# schematic.net
KiCad netlist of a schematic drawn in EasyEDA
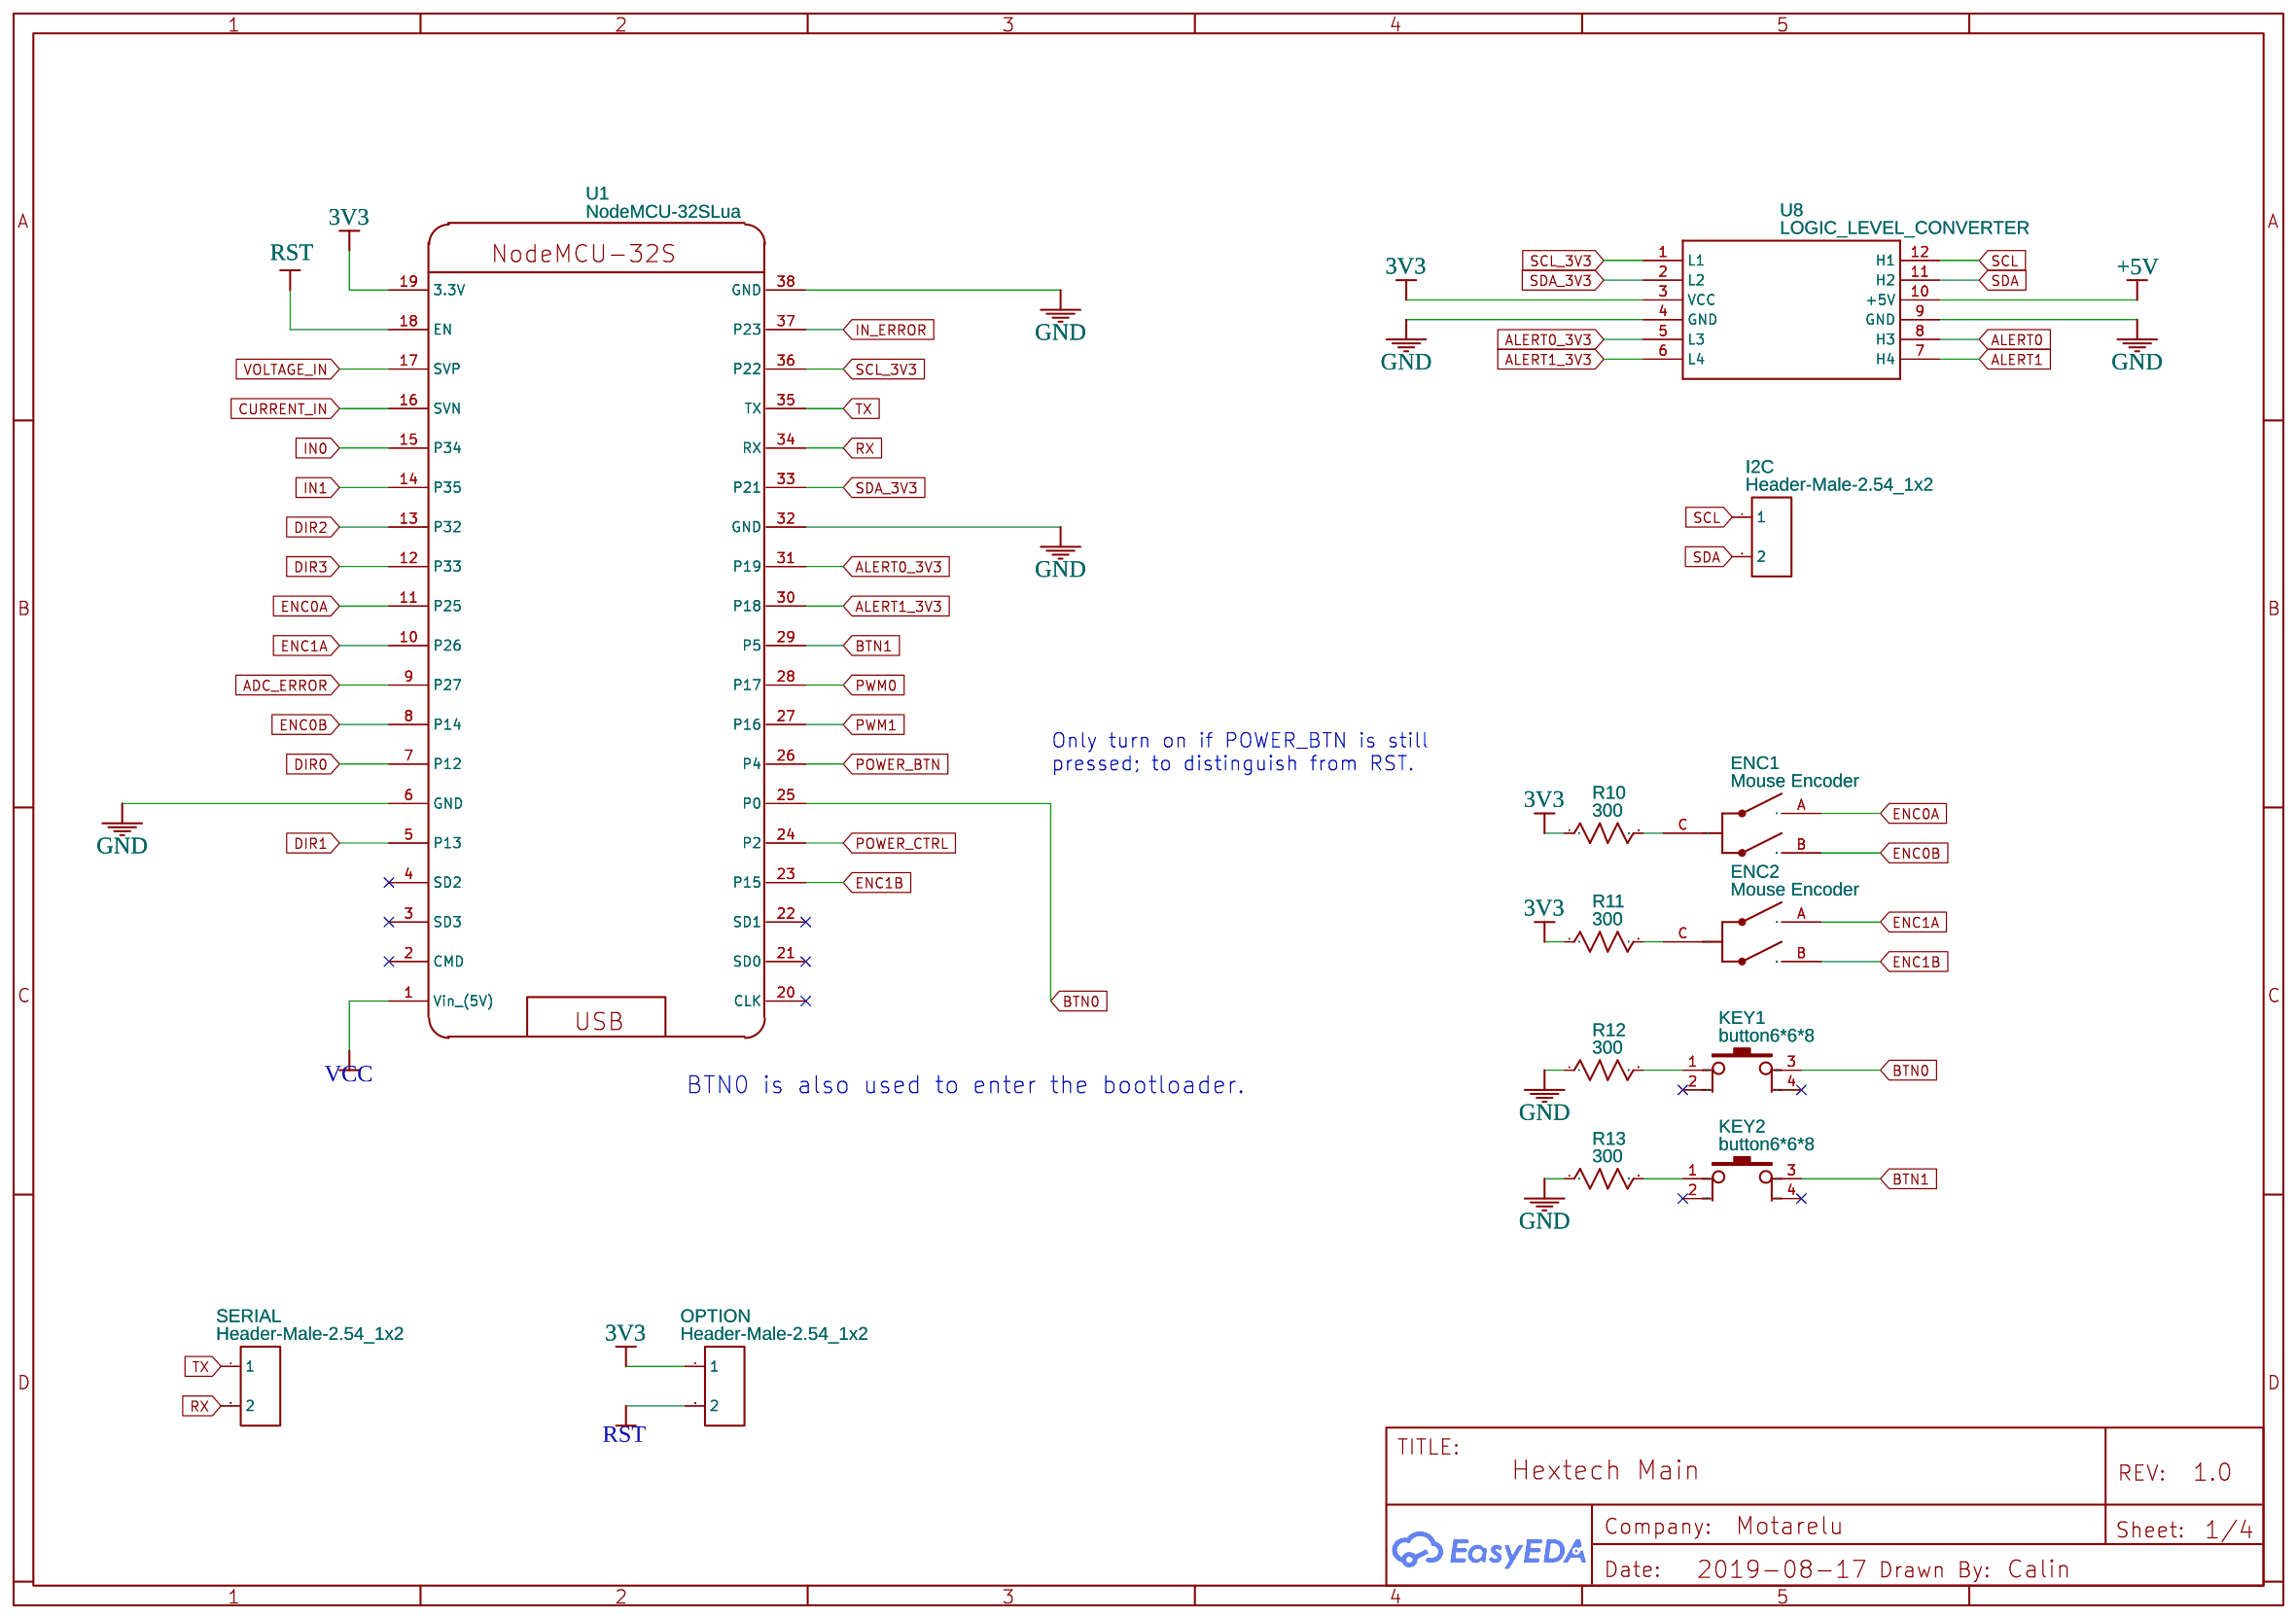
[diagram p0: Main]
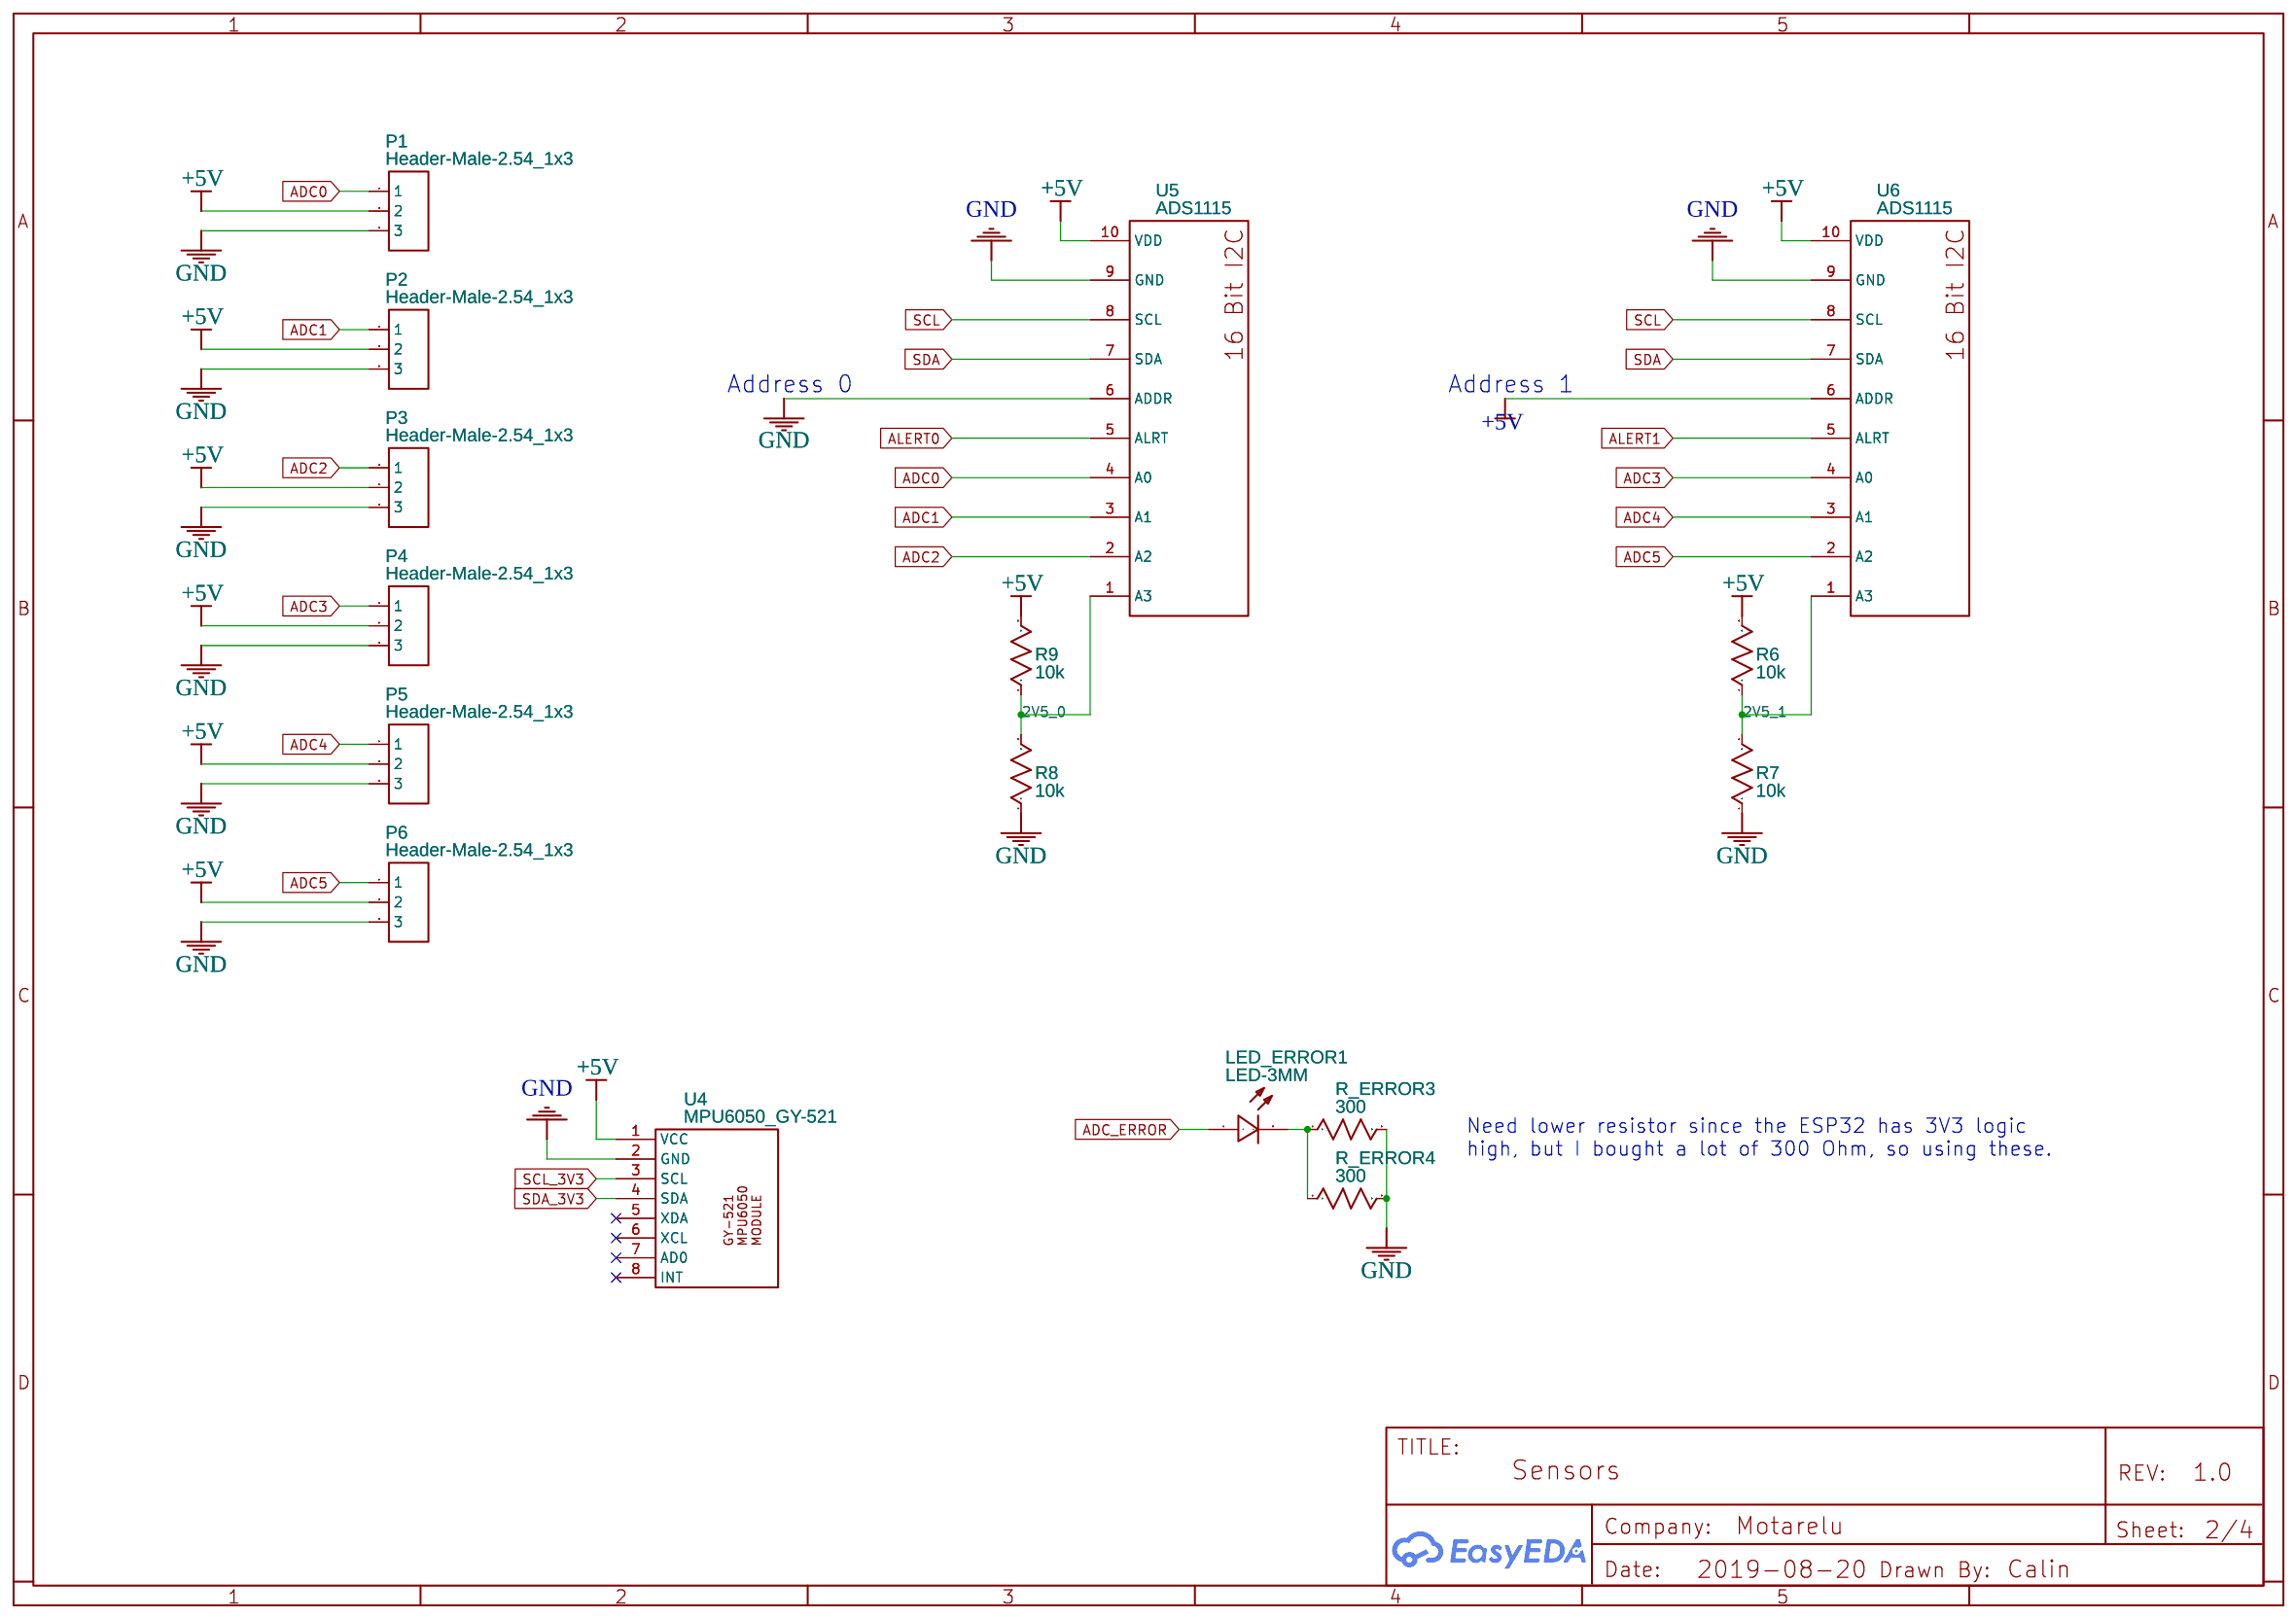
[diagram p1: Sensors]
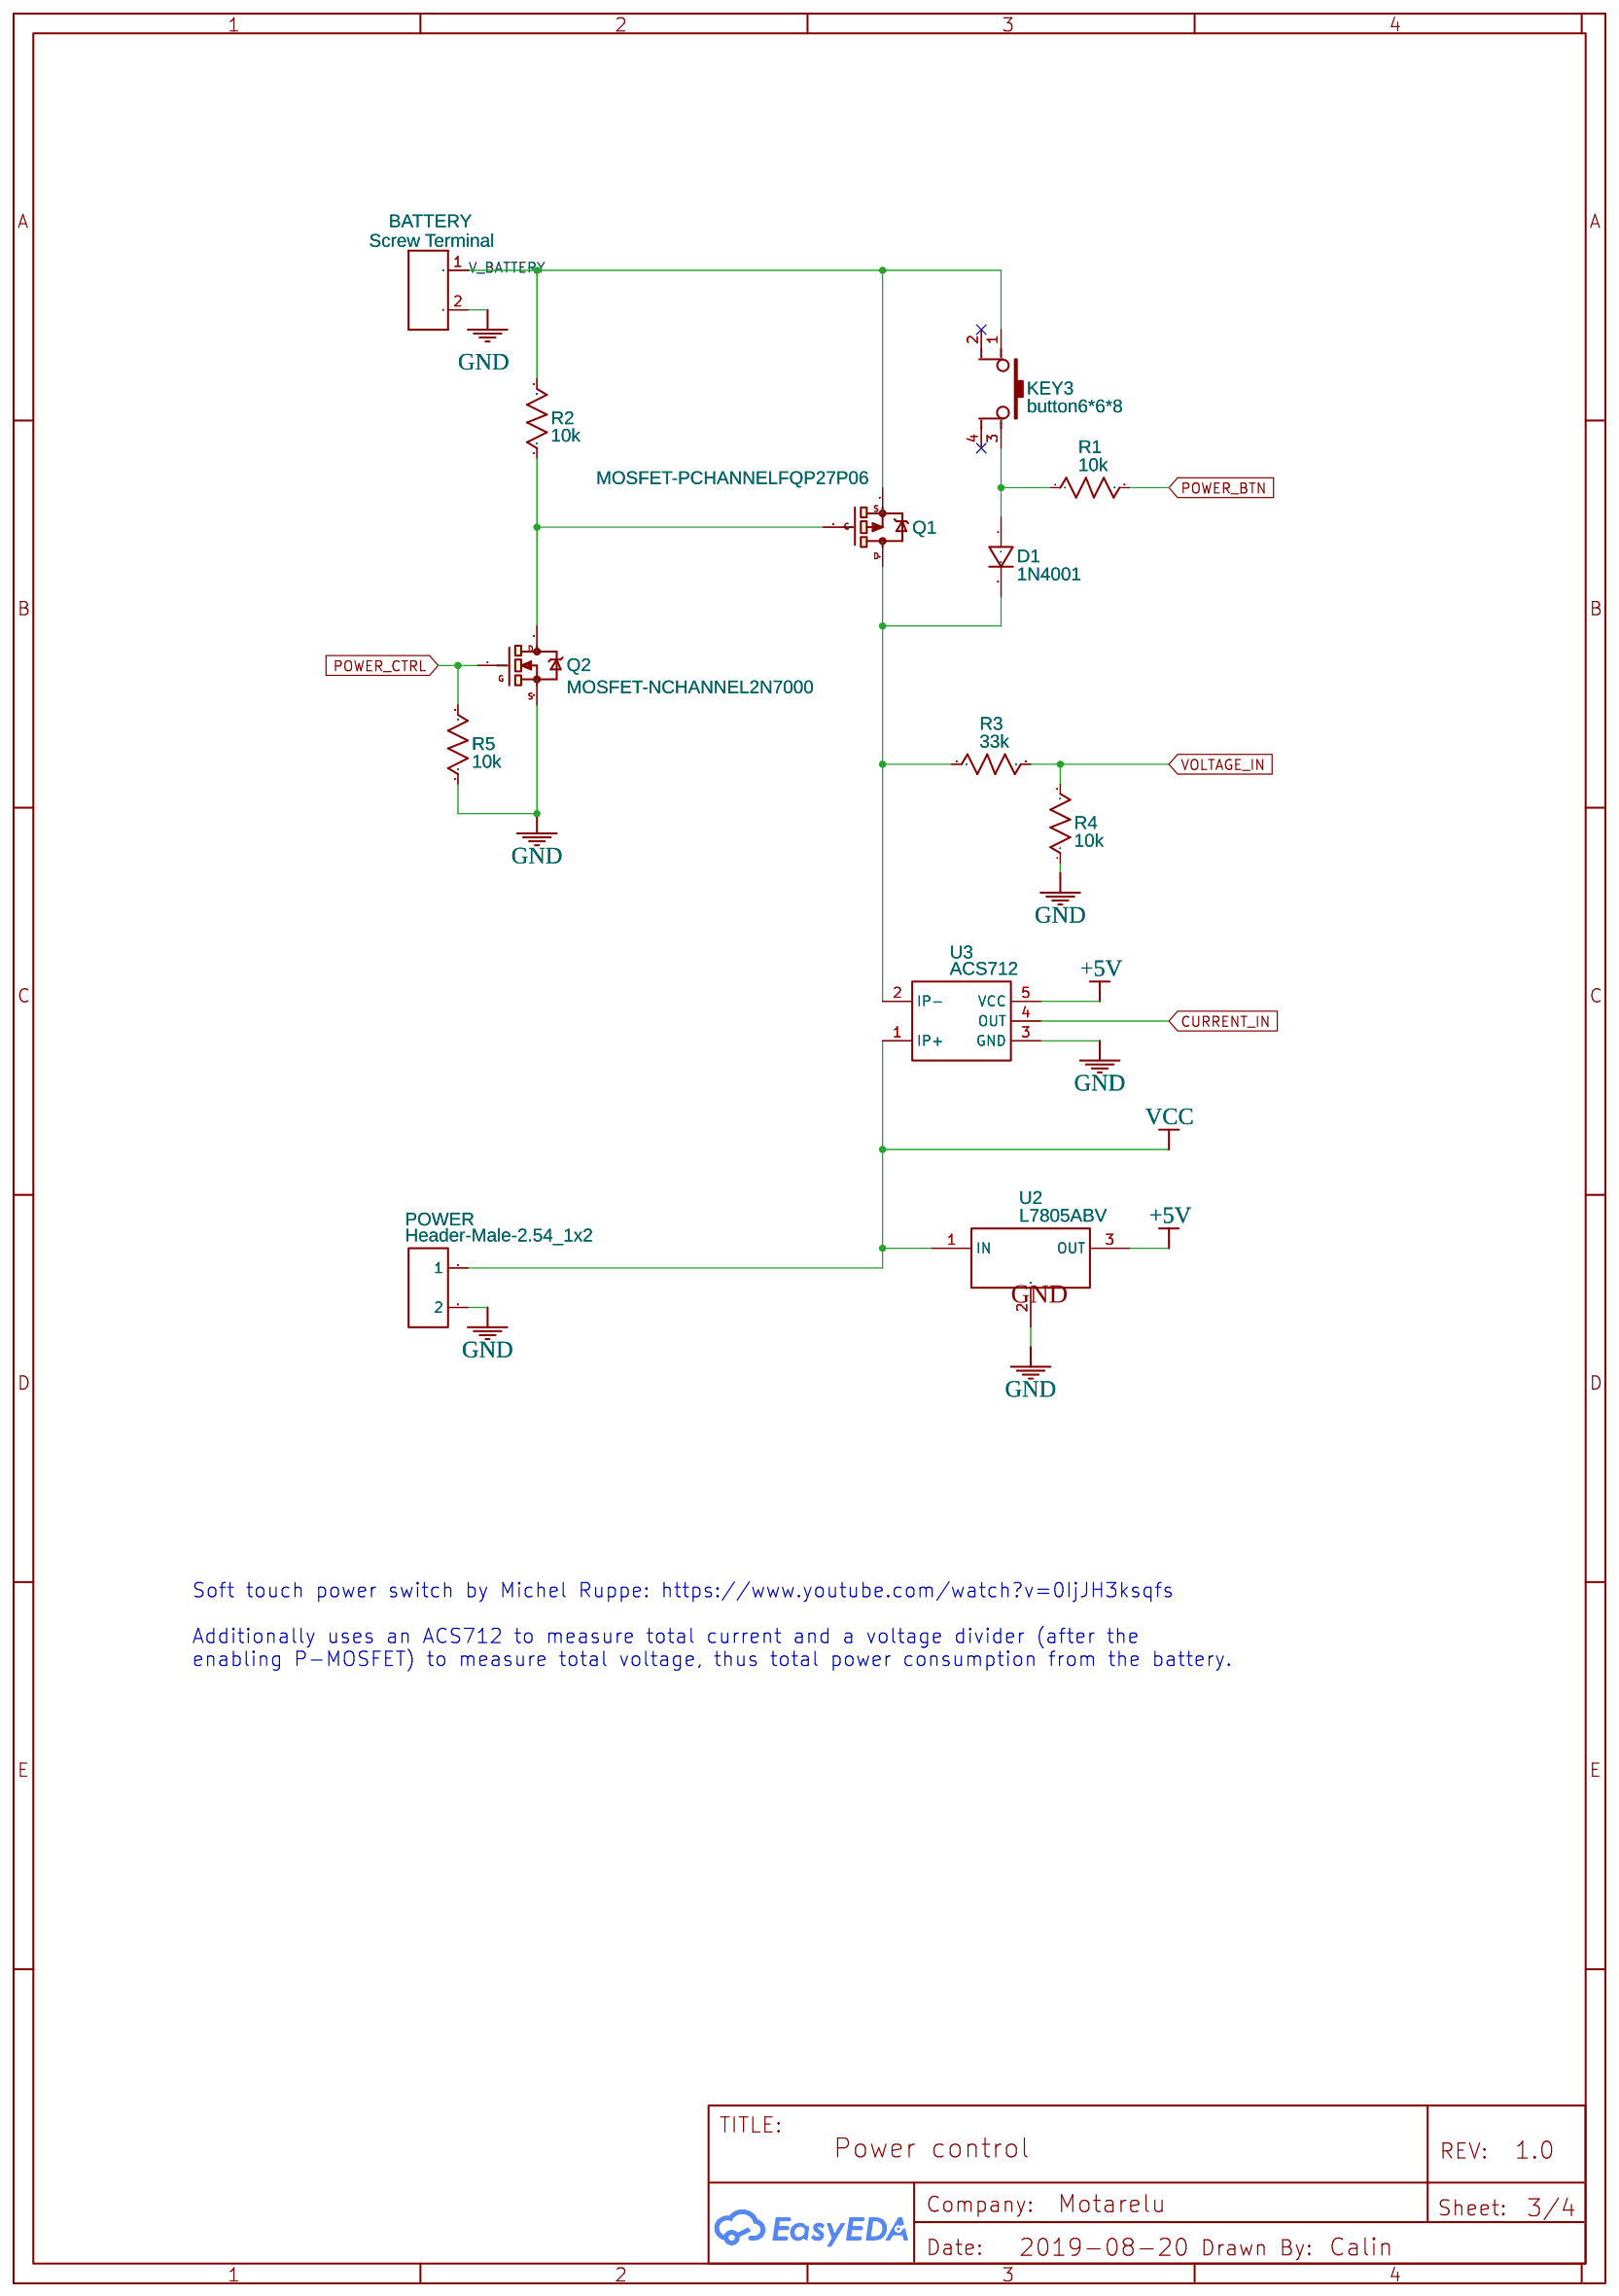
[diagram p2: Power]
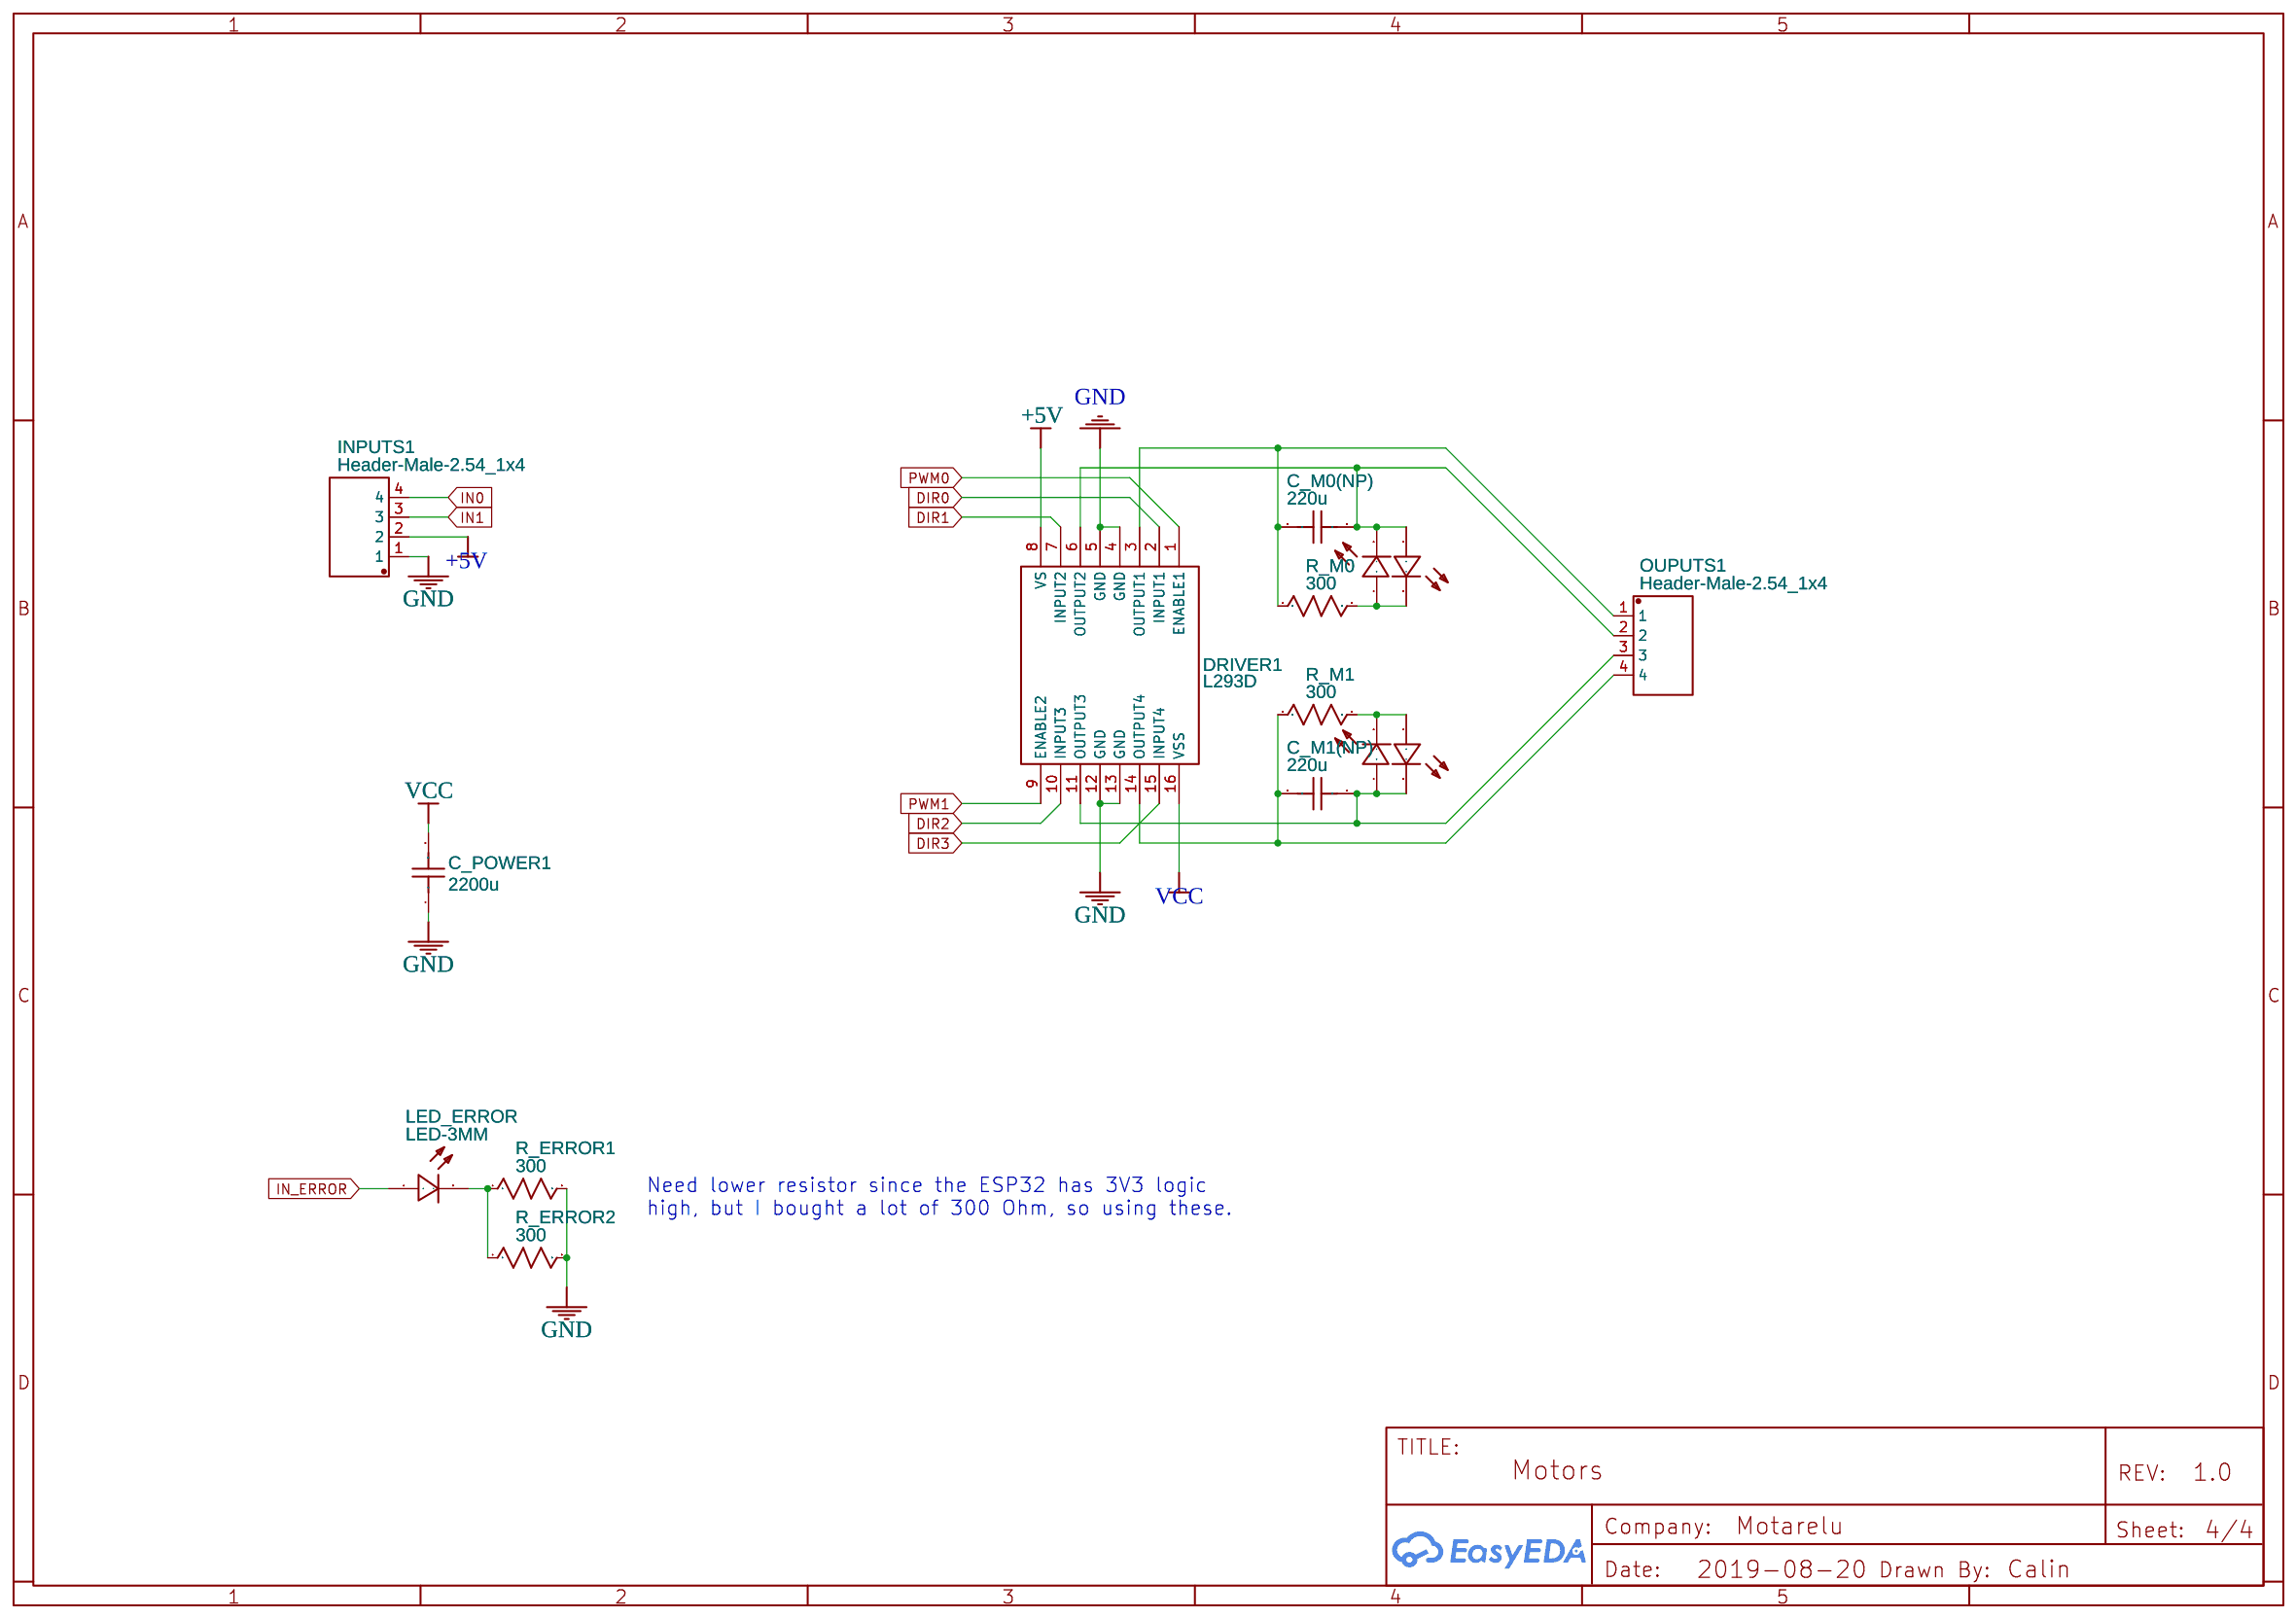
[diagram p3: Motors]

(export (version "E")
  (design (tool "Eeschema 10.0.6"))
  (components
    (comp (ref "ENC1") (value "Mouse Encoder") (libsource (lib "") (part "Unknown_875_415")))
    (comp (ref "ENC2") (value "Mouse Encoder") (libsource (lib "") (part "Unknown_875_470")))
    (comp (ref "I2C")
      (value "Header-Male-2.54_1x2")
      (fields (field (name "BOM_Manufacturer Part") "826629-2") (field (name "BOM_Supplier Part") "C86471"))
      (libsource (lib "") (part "Unknown_885_265"))
    )
    (comp (ref "KEY1")
      (value "button6*6*8")
      (fields (field (name "BOM_Supplier Part") "C59982"))
      (libsource (lib "") (part "Unknown_875_535"))
    )
    (comp (ref "KEY2")
      (value "button6*6*8")
      (fields (field (name "BOM_Supplier Part") "C59982"))
      (libsource (lib "") (part "Unknown_875_590"))
    )
    (comp (ref "OPTION")
      (value "Header-Male-2.54_1x2")
      (fields (field (name "BOM_Manufacturer Part") "826629-2") (field (name "BOM_Supplier Part") "C86471"))
      (libsource (lib "") (part "Unknown_355_695"))
    )
    (comp (ref "R10") (value "300") (libsource (lib "") (part "Res_AXIAL-0.3(1/8W)_US")))
    (comp (ref "R11") (value "300") (libsource (lib "") (part "Res_AXIAL-0.3(1/8W)_US")))
    (comp (ref "R12") (value "300") (libsource (lib "") (part "Res_AXIAL-0.3(1/8W)_US")))
    (comp (ref "R13") (value "300") (libsource (lib "") (part "Res_AXIAL-0.3(1/8W)_US")))
    (comp (ref "SERIAL")
      (value "Header-Male-2.54_1x2")
      (fields (field (name "BOM_Manufacturer Part") "826629-2") (field (name "BOM_Supplier Part") "C86471"))
      (libsource (lib "") (part "Unknown_120_695"))
    )
    (comp (ref "U1")
      (value "NodeMCU-32SLua")
      (fields (field (name "BOM_Supplier Part") "C111436"))
      (libsource (lib "") (part "Unknown_300_310"))
    )
    (comp (ref "U8") (value "LOGIC_LEVEL_CONVERTER") (libsource (lib "") (part "Unknown_905_150")))
    (comp (ref "LED_ERROR1")
      (value "LED-3MM")
      (fields
        (field (name "BOM_Manufacturer Part") "204-10SURD/S530-A3")
        (field (name "BOM_Supplier Part") "C99772")
      )
      (libsource (lib "") (part "Unknown_625_560"))
    )
    (comp (ref "P1")
      (value "Header-Male-2.54_1x3")
      (fields
        (field (name "BOM_Manufacturer Part") "Header2.54mm 1*3P")
        (field (name "BOM_Supplier Part") "C49257")
      )
      (libsource (lib "") (part "Unknown_195_100"))
    )
    (comp (ref "P2")
      (value "Header-Male-2.54_1x3")
      (fields
        (field (name "BOM_Manufacturer Part") "Header2.54mm 1*3P")
        (field (name "BOM_Supplier Part") "C49257")
      )
      (libsource (lib "") (part "Unknown_195_170"))
    )
    (comp (ref "P3")
      (value "Header-Male-2.54_1x3")
      (fields
        (field (name "BOM_Manufacturer Part") "Header2.54mm 1*3P")
        (field (name "BOM_Supplier Part") "C49257")
      )
      (libsource (lib "") (part "Unknown_195_240"))
    )
    (comp (ref "P4")
      (value "Header-Male-2.54_1x3")
      (fields
        (field (name "BOM_Manufacturer Part") "Header2.54mm 1*3P")
        (field (name "BOM_Supplier Part") "C49257")
      )
      (libsource (lib "") (part "Unknown_195_310"))
    )
    (comp (ref "P5")
      (value "Header-Male-2.54_1x3")
      (fields
        (field (name "BOM_Manufacturer Part") "Header2.54mm 1*3P")
        (field (name "BOM_Supplier Part") "C49257")
      )
      (libsource (lib "") (part "Unknown_195_380"))
    )
    (comp (ref "P6")
      (value "Header-Male-2.54_1x3")
      (fields
        (field (name "BOM_Manufacturer Part") "Header2.54mm 1*3P")
        (field (name "BOM_Supplier Part") "C49257")
      )
      (libsource (lib "") (part "Unknown_195_450"))
    )
    (comp (ref "R6") (value "10k") (libsource (lib "") (part "Res_AXIAL-0.3(1/8W)_US")))
    (comp (ref "R7") (value "10k") (libsource (lib "") (part "Res_AXIAL-0.3(1/8W)_US")))
    (comp (ref "R8") (value "10k") (libsource (lib "") (part "Res_AXIAL-0.3(1/8W)_US")))
    (comp (ref "R9") (value "10k") (libsource (lib "") (part "Res_AXIAL-0.3(1/8W)_US")))
    (comp (ref "R_ERROR3")
      (value "300")
      (fields (field (name "BOM_Manufacturer Part") "?"))
      (libsource (lib "") (part "Res_AXIAL-0.3(1/8W)_US_1"))
    )
    (comp (ref "R_ERROR4")
      (value "300")
      (fields (field (name "BOM_Manufacturer Part") "?"))
      (libsource (lib "") (part "Res_AXIAL-0.3(1/8W)_US_1"))
    )
    (comp (ref "U4")
      (value "MPU6050_GY-521")
      (fields (field (name "BOM_Manufacturer Part") "GY-521"))
      (libsource (lib "") (part "Unknown_325_605"))
    )
    (comp (ref "U5")
      (value "ADS1115")
      (fields (field (name "BOM_Supplier Part") "1528-1461-ND"))
      (libsource (lib "") (part "Unknown_625_105"))
    )
    (comp (ref "U6")
      (value "ADS1115")
      (fields (field (name "BOM_Supplier Part") "1528-1461-ND"))
      (libsource (lib "") (part "Unknown_990_105"))
    )
    (comp (ref "BATTERY")
      (value "Screw Terminal")
      (fields (field (name "BOM_Manufacturer Part") "?"))
      (libsource (lib "") (part "Unknown_215_140"))
    )
    (comp (ref "D1")
      (value "1N4001")
      (fields (field (name "BOM_Supplier Part") "C169150"))
      (libsource (lib "") (part "Unknown_500_275"))
    )
    (comp (ref "KEY3")
      (value "button6*6*8")
      (fields (field (name "BOM_Supplier Part") "C59982"))
      (libsource (lib "") (part "Unknown_500_190"))
    )
    (comp (ref "POWER")
      (value "Header-Male-2.54_1x2")
      (fields (field (name "BOM_Manufacturer Part") "826629-2") (field (name "BOM_Supplier Part") "C86471"))
      (libsource (lib "") (part "Unknown_215_645"))
    )
    (comp (ref "Q1") (value "MOSFET-PCHANNELFQP27P06") (libsource (lib "") (part "Unknown_430_260")))
    (comp (ref "Q2") (value "MOSFET-NCHANNEL2N7000") (libsource (lib "") (part "Unknown_255_330")))
    (comp (ref "R1") (value "10k") (libsource (lib "") (part "Res_AXIAL-0.3(1/8W)_US")))
    (comp (ref "R2") (value "10k") (libsource (lib "") (part "Res_AXIAL-0.3(1/8W)_US_1")))
    (comp (ref "R3") (value "33k") (libsource (lib "") (part "Res_AXIAL-0.3(1/8W)_US")))
    (comp (ref "R4") (value "10k") (libsource (lib "") (part "Res_AXIAL-0.3(1/8W)_US_1")))
    (comp (ref "R5") (value "10k") (libsource (lib "") (part "Res_AXIAL-0.3(1/8W)_US_1")))
    (comp (ref "U2")
      (value "L7805ABV")
      (fields (field (name "BOM_Supplier Part") "C16807"))
      (libsource (lib "") (part "Unknown_515_640"))
    )
    (comp (ref "U3") (value "ACS712") (libsource (lib "") (part "Unknown_480_510")))
    (comp (ref "C_M0(NP)")
      (value "220u")
      (fields (field (name "BOM_Manufacturer Part") "?"))
      (libsource (lib "") (part "Cap_RAD-0.1_US_2"))
    )
    (comp (ref "C_M1(NP)")
      (value "220u")
      (fields (field (name "BOM_Manufacturer Part") "?"))
      (libsource (lib "") (part "Cap_RAD-0.1_US_1"))
    )
    (comp (ref "C_POWER1")
      (value "2200u")
      (fields (field (name "BOM_Manufacturer Part") "?"))
      (libsource (lib "") (part "Cap_RAD-0.1_US"))
    )
    (comp (ref "DRIVER1")
      (value "L293D")
      (fields (field (name "BOM_Supplier Part") "C12340"))
      (libsource (lib "") (part "Unknown_550_330"))
    )
    (comp (ref "INPUTS1")
      (value "Header-Male-2.54_1x4")
      (fields
        (field (name "BOM_Manufacturer Part") "210S-1*4P L=11.6MMGold-plated black")
        (field (name "BOM_Supplier Part") "C124378")
      )
      (libsource (lib "") (part "Unknown_180_260"))
    )
    (comp (ref "LED_ERROR")
      (value "LED-3MM")
      (fields
        (field (name "BOM_Manufacturer Part") "204-10SURD/S530-A3")
        (field (name "BOM_Supplier Part") "C99772")
      )
      (libsource (lib "") (part "Unknown_210_590"))
    )
    (comp (ref "LED_M0A")
      (value "LED-3MM")
      (fields
        (field (name "BOM_Manufacturer Part") "204-10SURD/S530-A3")
        (field (name "BOM_Supplier Part") "C99772")
      )
      (libsource (lib "") (part "Unknown_685_280"))
    )
    (comp (ref "LED_M0B")
      (value "LED-3MM")
      (fields
        (field (name "BOM_Manufacturer Part") "204-10SURD/S530-A3")
        (field (name "BOM_Supplier Part") "C99772")
      )
      (libsource (lib "") (part "Unknown_710_280"))
    )
    (comp (ref "LED_M1A")
      (value "LED-3MM")
      (fields
        (field (name "BOM_Manufacturer Part") "204-10SURD/S530-A3")
        (field (name "BOM_Supplier Part") "C99772")
      )
      (libsource (lib "") (part "Unknown_685_375"))
    )
    (comp (ref "LED_M1B")
      (value "LED-3MM")
      (fields
        (field (name "BOM_Manufacturer Part") "204-10SURD/S530-A3")
        (field (name "BOM_Supplier Part") "C99772")
      )
      (libsource (lib "") (part "Unknown_710_375"))
    )
    (comp (ref "OUPUTS1")
      (value "Header-Male-2.54_1x4")
      (fields
        (field (name "BOM_Manufacturer Part") "210S-1*4P L=11.6MMGold-plated black")
        (field (name "BOM_Supplier Part") "C124378")
      )
      (libsource (lib "") (part "Unknown_830_320"))
    )
    (comp (ref "R_ERROR1")
      (value "300")
      (fields (field (name "BOM_Manufacturer Part") "?"))
      (libsource (lib "") (part "Res_AXIAL-0.3(1/8W)_US"))
    )
    (comp (ref "R_ERROR2")
      (value "300")
      (fields (field (name "BOM_Manufacturer Part") "?"))
      (libsource (lib "") (part "Res_AXIAL-0.3(1/8W)_US"))
    )
    (comp (ref "R_M0")
      (value "300")
      (fields (field (name "BOM_Manufacturer Part") "?"))
      (libsource (lib "") (part "Res_AXIAL-0.3(1/8W)_US_1"))
    )
    (comp (ref "R_M1")
      (value "300")
      (fields (field (name "BOM_Manufacturer Part") "?"))
      (libsource (lib "") (part "Res_AXIAL-0.3(1/8W)_US_1"))
    )
  )
  (nets
    (net (code "1") (name "+5V") (class "Default")
      (node (ref "DRIVER1") (pin "8") (pinfunction "VS_8") (pintype "unspecified"))
      (node (ref "INPUTS1") (pin "2") (pinfunction "2_2") (pintype "unspecified"))
      (node (ref "P1") (pin "2") (pinfunction "2_2") (pintype "input"))
      (node (ref "P2") (pin "2") (pinfunction "2_2") (pintype "input"))
      (node (ref "P3") (pin "2") (pinfunction "2_2") (pintype "input"))
      (node (ref "P4") (pin "2") (pinfunction "2_2") (pintype "input"))
      (node (ref "P5") (pin "2") (pinfunction "2_2") (pintype "input"))
      (node (ref "P6") (pin "2") (pinfunction "2_2") (pintype "input"))
      (node (ref "R6") (pin "2") (pinfunction "2_2") (pintype "unspecified"))
      (node (ref "R9") (pin "2") (pinfunction "2_2") (pintype "unspecified"))
      (node (ref "U2") (pin "3") (pinfunction "OUT_3") (pintype "passive"))
      (node (ref "U3") (pin "5") (pinfunction "VCC_5") (pintype "passive"))
      (node (ref "U4") (pin "1") (pinfunction "VCC_1") (pintype "unspecified"))
      (node (ref "U5") (pin "10") (pinfunction "VDD_10") (pintype "unspecified"))
      (node (ref "U6") (pin "10") (pinfunction "VDD_10") (pintype "unspecified"))
      (node (ref "U6") (pin "6") (pinfunction "ADDR_6") (pintype "unspecified"))
      (node (ref "U8") (pin "10") (pinfunction "+5V_10") (pintype "passive"))
    )
    (net (code "2") (name "2V5_0") (class "Default")
      (node (ref "R8") (pin "2") (pinfunction "2_2") (pintype "unspecified"))
      (node (ref "R9") (pin "1") (pinfunction "1_1") (pintype "unspecified"))
      (node (ref "U5") (pin "1") (pinfunction "A3_1") (pintype "unspecified"))
    )
    (net (code "3") (name "2V5_1") (class "Default")
      (node (ref "R6") (pin "1") (pinfunction "1_1") (pintype "unspecified"))
      (node (ref "R7") (pin "2") (pinfunction "2_2") (pintype "unspecified"))
      (node (ref "U6") (pin "1") (pinfunction "A3_1") (pintype "unspecified"))
    )
    (net (code "4") (name "3V3") (class "Default")
      (node (ref "OPTION") (pin "1") (pinfunction "1_1") (pintype "unspecified"))
      (node (ref "R10") (pin "1") (pinfunction "1_1") (pintype "unspecified"))
      (node (ref "R11") (pin "1") (pinfunction "1_1") (pintype "unspecified"))
      (node (ref "U1") (pin "19") (pinfunction "3.3V_19") (pintype "unspecified"))
      (node (ref "U8") (pin "3") (pinfunction "VCC_3") (pintype "passive"))
    )
    (net (code "5") (name "ADC0") (class "Default")
      (node (ref "P1") (pin "1") (pinfunction "1_1") (pintype "input"))
      (node (ref "U5") (pin "4") (pinfunction "A0_4") (pintype "unspecified"))
    )
    (net (code "6") (name "ADC1") (class "Default")
      (node (ref "P2") (pin "1") (pinfunction "1_1") (pintype "input"))
      (node (ref "U5") (pin "3") (pinfunction "A1_3") (pintype "unspecified"))
    )
    (net (code "7") (name "ADC2") (class "Default")
      (node (ref "P3") (pin "1") (pinfunction "1_1") (pintype "input"))
      (node (ref "U5") (pin "2") (pinfunction "A2_2") (pintype "unspecified"))
    )
    (net (code "8") (name "ADC3") (class "Default")
      (node (ref "P4") (pin "1") (pinfunction "1_1") (pintype "input"))
      (node (ref "U6") (pin "4") (pinfunction "A0_4") (pintype "unspecified"))
    )
    (net (code "9") (name "ADC4") (class "Default")
      (node (ref "P5") (pin "1") (pinfunction "1_1") (pintype "input"))
      (node (ref "U6") (pin "3") (pinfunction "A1_3") (pintype "unspecified"))
    )
    (net (code "10") (name "ADC5") (class "Default")
      (node (ref "P6") (pin "1") (pinfunction "1_1") (pintype "input"))
      (node (ref "U6") (pin "2") (pinfunction "A2_2") (pintype "unspecified"))
    )
    (net (code "11") (name "ADC_ERROR") (class "Default")
      (node (ref "LED_ERROR1") (pin "1") (pinfunction "+_1") (pintype "unspecified"))
      (node (ref "U1") (pin "9") (pinfunction "P27_9") (pintype "unspecified"))
    )
    (net (code "12") (name "ALERT0") (class "Default")
      (node (ref "U5") (pin "5") (pinfunction "ALRT_5") (pintype "unspecified"))
      (node (ref "U8") (pin "8") (pinfunction "H3_8") (pintype "unspecified"))
    )
    (net (code "13") (name "ALERT0_3V3") (class "Default")
      (node (ref "U1") (pin "31") (pinfunction "P19_31") (pintype "unspecified"))
      (node (ref "U8") (pin "5") (pinfunction "L3_5") (pintype "unspecified"))
    )
    (net (code "14") (name "ALERT1") (class "Default")
      (node (ref "U6") (pin "5") (pinfunction "ALRT_5") (pintype "unspecified"))
      (node (ref "U8") (pin "7") (pinfunction "H4_7") (pintype "unspecified"))
    )
    (net (code "15") (name "ALERT1_3V3") (class "Default")
      (node (ref "U1") (pin "30") (pinfunction "P18_30") (pintype "unspecified"))
      (node (ref "U8") (pin "6") (pinfunction "L4_6") (pintype "unspecified"))
    )
    (net (code "16") (name "BTN0") (class "Default")
      (node (ref "KEY1") (pin "3") (pinfunction "3_3") (pintype "input"))
      (node (ref "U1") (pin "25") (pinfunction "P0_25") (pintype "unspecified"))
    )
    (net (code "17") (name "BTN1") (class "Default")
      (node (ref "KEY2") (pin "3") (pinfunction "3_3") (pintype "input"))
      (node (ref "U1") (pin "29") (pinfunction "P5_29") (pintype "unspecified"))
    )
    (net (code "18") (name "CURRENT_IN") (class "Default")
      (node (ref "U1") (pin "16") (pinfunction "SVN_16") (pintype "unspecified"))
      (node (ref "U3") (pin "4") (pinfunction "OUT_4") (pintype "output"))
    )
    (net (code "19") (name "DIR0") (class "Default")
      (node (ref "DRIVER1") (pin "2") (pinfunction "INPUT1_2") (pintype "unspecified"))
      (node (ref "U1") (pin "7") (pinfunction "P12_7") (pintype "unspecified"))
    )
    (net (code "20") (name "DIR1") (class "Default")
      (node (ref "DRIVER1") (pin "7") (pinfunction "INPUT2_7") (pintype "unspecified"))
      (node (ref "U1") (pin "5") (pinfunction "P13_5") (pintype "unspecified"))
    )
    (net (code "21") (name "DIR2") (class "Default")
      (node (ref "DRIVER1") (pin "10") (pinfunction "INPUT3_10") (pintype "unspecified"))
      (node (ref "U1") (pin "13") (pinfunction "P32_13") (pintype "unspecified"))
    )
    (net (code "22") (name "DIR3") (class "Default")
      (node (ref "DRIVER1") (pin "15") (pinfunction "INPUT4_15") (pintype "unspecified"))
      (node (ref "U1") (pin "12") (pinfunction "P33_12") (pintype "unspecified"))
    )
    (net (code "23") (name "ENC0A") (class "Default")
      (node (ref "ENC1") (pin "A") (pinfunction "A_A") (pintype "unspecified"))
      (node (ref "U1") (pin "11") (pinfunction "P25_11") (pintype "unspecified"))
    )
    (net (code "24") (name "ENC0B") (class "Default")
      (node (ref "ENC1") (pin "B") (pinfunction "B_B") (pintype "unspecified"))
      (node (ref "U1") (pin "8") (pinfunction "P14_8") (pintype "unspecified"))
    )
    (net (code "25") (name "ENC1A") (class "Default")
      (node (ref "ENC2") (pin "A") (pinfunction "A_A") (pintype "unspecified"))
      (node (ref "U1") (pin "10") (pinfunction "P26_10") (pintype "unspecified"))
    )
    (net (code "26") (name "ENC1B") (class "Default")
      (node (ref "ENC2") (pin "B") (pinfunction "B_B") (pintype "unspecified"))
      (node (ref "U1") (pin "23") (pinfunction "P15_23") (pintype "unspecified"))
    )
    (net (code "27") (name "GND") (class "Default")
      (node (ref "BATTERY") (pin "2") (pinfunction "2_2") (pintype "unspecified"))
      (node (ref "C_POWER1") (pin "1") (pinfunction "1_1") (pintype "unspecified"))
      (node (ref "DRIVER1") (pin "12") (pinfunction "GND_12") (pintype "unspecified"))
      (node (ref "DRIVER1") (pin "13") (pinfunction "GND_13") (pintype "unspecified"))
      (node (ref "DRIVER1") (pin "4") (pinfunction "GND_4") (pintype "unspecified"))
      (node (ref "DRIVER1") (pin "5") (pinfunction "GND_5") (pintype "unspecified"))
      (node (ref "INPUTS1") (pin "1") (pinfunction "1_1") (pintype "unspecified"))
      (node (ref "P1") (pin "3") (pinfunction "3_3") (pintype "input"))
      (node (ref "P2") (pin "3") (pinfunction "3_3") (pintype "input"))
      (node (ref "P3") (pin "3") (pinfunction "3_3") (pintype "input"))
      (node (ref "P4") (pin "3") (pinfunction "3_3") (pintype "input"))
      (node (ref "P5") (pin "3") (pinfunction "3_3") (pintype "input"))
      (node (ref "P6") (pin "3") (pinfunction "3_3") (pintype "input"))
      (node (ref "POWER") (pin "2") (pinfunction "2_2") (pintype "unspecified"))
      (node (ref "Q2") (pin "1") (pinfunction "S_1") (pintype "unspecified"))
      (node (ref "R12") (pin "1") (pinfunction "1_1") (pintype "unspecified"))
      (node (ref "R13") (pin "1") (pinfunction "1_1") (pintype "unspecified"))
      (node (ref "R4") (pin "1") (pinfunction "1_1") (pintype "unspecified"))
      (node (ref "R5") (pin "1") (pinfunction "1_1") (pintype "unspecified"))
      (node (ref "R7") (pin "1") (pinfunction "1_1") (pintype "unspecified"))
      (node (ref "R8") (pin "1") (pinfunction "1_1") (pintype "unspecified"))
      (node (ref "R_ERROR1") (pin "2") (pinfunction "2_2") (pintype "unspecified"))
      (node (ref "R_ERROR2") (pin "2") (pinfunction "2_2") (pintype "unspecified"))
      (node (ref "R_ERROR3") (pin "2") (pinfunction "2_2") (pintype "unspecified"))
      (node (ref "R_ERROR4") (pin "2") (pinfunction "2_2") (pintype "unspecified"))
      (node (ref "U1") (pin "32") (pinfunction "GND_32") (pintype "unspecified"))
      (node (ref "U1") (pin "38") (pinfunction "GND_38") (pintype "unspecified"))
      (node (ref "U1") (pin "6") (pinfunction "GND_6") (pintype "unspecified"))
      (node (ref "U2") (pin "2") (pinfunction "GND_2") (pintype "passive"))
      (node (ref "U3") (pin "3") (pinfunction "GND_3") (pintype "passive"))
      (node (ref "U4") (pin "2") (pinfunction "GND_2") (pintype "unspecified"))
      (node (ref "U5") (pin "6") (pinfunction "ADDR_6") (pintype "unspecified"))
      (node (ref "U5") (pin "9") (pinfunction "GND_9") (pintype "unspecified"))
      (node (ref "U6") (pin "9") (pinfunction "GND_9") (pintype "unspecified"))
      (node (ref "U8") (pin "4") (pinfunction "GND_4") (pintype "passive"))
      (node (ref "U8") (pin "9") (pinfunction "GND_9") (pintype "passive"))
    )
    (net (code "28") (name "IN0") (class "Default")
      (node (ref "INPUTS1") (pin "4") (pinfunction "4_4") (pintype "unspecified"))
      (node (ref "U1") (pin "15") (pinfunction "P34_15") (pintype "unspecified"))
    )
    (net (code "29") (name "IN1") (class "Default")
      (node (ref "INPUTS1") (pin "3") (pinfunction "3_3") (pintype "unspecified"))
      (node (ref "U1") (pin "14") (pinfunction "P35_14") (pintype "unspecified"))
    )
    (net (code "30") (name "IN_ERROR") (class "Default")
      (node (ref "LED_ERROR") (pin "1") (pinfunction "+_1") (pintype "unspecified"))
      (node (ref "U1") (pin "37") (pinfunction "P23_37") (pintype "unspecified"))
    )
    (net (code "31") (name "Net-(D1-Pad1)") (class "Default")
      (node (ref "D1") (pin "1") (pinfunction "1_1") (pintype "unspecified"))
      (node (ref "KEY3") (pin "3") (pinfunction "3_3") (pintype "input"))
      (node (ref "R1") (pin "1") (pinfunction "1_1") (pintype "unspecified"))
    )
    (net (code "32") (name "Net-(DRIVER1-OUTPUT1)") (class "Default")
      (node (ref "C_M0(NP)") (pin "2") (pinfunction "2_2") (pintype "unspecified"))
      (node (ref "DRIVER1") (pin "3") (pinfunction "OUTPUT1_3") (pintype "unspecified"))
      (node (ref "OUPUTS1") (pin "1") (pinfunction "1_1") (pintype "unspecified"))
      (node (ref "R_M0") (pin "1") (pinfunction "1_1") (pintype "unspecified"))
    )
    (net (code "33") (name "Net-(DRIVER1-OUTPUT2)") (class "Default")
      (node (ref "C_M0(NP)") (pin "1") (pinfunction "1_1") (pintype "unspecified"))
      (node (ref "DRIVER1") (pin "6") (pinfunction "OUTPUT2_6") (pintype "unspecified"))
      (node (ref "LED_M0A") (pin "2") (pinfunction "-_2") (pintype "unspecified"))
      (node (ref "LED_M0B") (pin "1") (pinfunction "+_1") (pintype "unspecified"))
      (node (ref "OUPUTS1") (pin "2") (pinfunction "2_2") (pintype "unspecified"))
    )
    (net (code "34") (name "Net-(DRIVER1-OUTPUT3)") (class "Default")
      (node (ref "C_M1(NP)") (pin "1") (pinfunction "1_1") (pintype "unspecified"))
      (node (ref "DRIVER1") (pin "11") (pinfunction "OUTPUT3_11") (pintype "unspecified"))
      (node (ref "LED_M1A") (pin "1") (pinfunction "+_1") (pintype "unspecified"))
      (node (ref "LED_M1B") (pin "2") (pinfunction "-_2") (pintype "unspecified"))
      (node (ref "OUPUTS1") (pin "3") (pinfunction "3_3") (pintype "unspecified"))
    )
    (net (code "35") (name "Net-(DRIVER1-OUTPUT4)") (class "Default")
      (node (ref "C_M1(NP)") (pin "2") (pinfunction "2_2") (pintype "unspecified"))
      (node (ref "DRIVER1") (pin "14") (pinfunction "OUTPUT4_14") (pintype "unspecified"))
      (node (ref "OUPUTS1") (pin "4") (pinfunction "4_4") (pintype "unspecified"))
      (node (ref "R_M1") (pin "1") (pinfunction "1_1") (pintype "unspecified"))
    )
    (net (code "36") (name "Net-(ENC1-PadC)") (class "Default")
      (node (ref "ENC1") (pin "C") (pinfunction "C_C") (pintype "unspecified"))
      (node (ref "R10") (pin "2") (pinfunction "2_2") (pintype "unspecified"))
    )
    (net (code "37") (name "Net-(ENC2-PadC)") (class "Default")
      (node (ref "ENC2") (pin "C") (pinfunction "C_C") (pintype "unspecified"))
      (node (ref "R11") (pin "2") (pinfunction "2_2") (pintype "unspecified"))
    )
    (net (code "38") (name "Net-(KEY1-Pad1)") (class "Default")
      (node (ref "KEY1") (pin "1") (pinfunction "1_1") (pintype "input"))
      (node (ref "R12") (pin "2") (pinfunction "2_2") (pintype "unspecified"))
    )
    (net (code "39") (name "Net-(KEY2-Pad1)") (class "Default")
      (node (ref "KEY2") (pin "1") (pinfunction "1_1") (pintype "input"))
      (node (ref "R13") (pin "2") (pinfunction "2_2") (pintype "unspecified"))
    )
    (net (code "40") (name "Net-(LED_ERROR--)") (class "Default")
      (node (ref "LED_ERROR") (pin "2") (pinfunction "-_2") (pintype "unspecified"))
      (node (ref "R_ERROR1") (pin "1") (pinfunction "1_1") (pintype "unspecified"))
      (node (ref "R_ERROR2") (pin "1") (pinfunction "1_1") (pintype "unspecified"))
    )
    (net (code "41") (name "Net-(LED_ERROR1--)") (class "Default")
      (node (ref "LED_ERROR1") (pin "2") (pinfunction "-_2") (pintype "unspecified"))
      (node (ref "R_ERROR3") (pin "1") (pinfunction "1_1") (pintype "unspecified"))
      (node (ref "R_ERROR4") (pin "1") (pinfunction "1_1") (pintype "unspecified"))
    )
    (net (code "42") (name "Net-(LED_M0A-+)") (class "Default")
      (node (ref "LED_M0A") (pin "1") (pinfunction "+_1") (pintype "unspecified"))
      (node (ref "LED_M0B") (pin "2") (pinfunction "-_2") (pintype "unspecified"))
      (node (ref "R_M0") (pin "2") (pinfunction "2_2") (pintype "unspecified"))
    )
    (net (code "43") (name "Net-(LED_M1A--)") (class "Default")
      (node (ref "LED_M1A") (pin "2") (pinfunction "-_2") (pintype "unspecified"))
      (node (ref "LED_M1B") (pin "1") (pinfunction "+_1") (pintype "unspecified"))
      (node (ref "R_M1") (pin "2") (pinfunction "2_2") (pintype "unspecified"))
    )
    (net (code "44") (name "Net-(Q1-D)") (class "Default")
      (node (ref "D1") (pin "2") (pinfunction "2_2") (pintype "unspecified"))
      (node (ref "Q1") (pin "2") (pinfunction "D_2") (pintype "unspecified"))
      (node (ref "R3") (pin "1") (pinfunction "1_1") (pintype "unspecified"))
      (node (ref "U3") (pin "2") (pinfunction "IP-_2") (pintype "input"))
    )
    (net (code "45") (name "Net-(Q1-G)") (class "Default")
      (node (ref "Q1") (pin "1") (pinfunction "G_1") (pintype "unspecified"))
      (node (ref "Q2") (pin "3") (pinfunction "D_3") (pintype "unspecified"))
      (node (ref "R2") (pin "1") (pinfunction "1_1") (pintype "unspecified"))
    )
    (net (code "46") (name "POWER_BTN") (class "Default")
      (node (ref "R1") (pin "2") (pinfunction "2_2") (pintype "unspecified"))
      (node (ref "U1") (pin "26") (pinfunction "P4_26") (pintype "unspecified"))
    )
    (net (code "47") (name "POWER_CTRL") (class "Default")
      (node (ref "Q2") (pin "2") (pinfunction "G_2") (pintype "unspecified"))
      (node (ref "R5") (pin "2") (pinfunction "2_2") (pintype "unspecified"))
      (node (ref "U1") (pin "24") (pinfunction "P2_24") (pintype "unspecified"))
    )
    (net (code "48") (name "PWM0") (class "Default")
      (node (ref "DRIVER1") (pin "1") (pinfunction "ENABLE1_1") (pintype "unspecified"))
      (node (ref "U1") (pin "28") (pinfunction "P17_28") (pintype "unspecified"))
    )
    (net (code "49") (name "PWM1") (class "Default")
      (node (ref "DRIVER1") (pin "9") (pinfunction "ENABLE2_9") (pintype "unspecified"))
      (node (ref "U1") (pin "27") (pinfunction "P16_27") (pintype "unspecified"))
    )
    (net (code "50") (name "RST") (class "Default")
      (node (ref "OPTION") (pin "2") (pinfunction "2_2") (pintype "unspecified"))
      (node (ref "U1") (pin "18") (pinfunction "EN_18") (pintype "unspecified"))
    )
    (net (code "51") (name "RX") (class "Default")
      (node (ref "SERIAL") (pin "2") (pinfunction "2_2") (pintype "unspecified"))
      (node (ref "U1") (pin "34") (pinfunction "RX_34") (pintype "unspecified"))
    )
    (net (code "52") (name "SCL") (class "Default")
      (node (ref "I2C") (pin "1") (pinfunction "1_1") (pintype "unspecified"))
      (node (ref "U5") (pin "8") (pinfunction "SCL_8") (pintype "unspecified"))
      (node (ref "U6") (pin "8") (pinfunction "SCL_8") (pintype "unspecified"))
      (node (ref "U8") (pin "12") (pinfunction "H1_12") (pintype "unspecified"))
    )
    (net (code "53") (name "SCL_3V3") (class "Default")
      (node (ref "U1") (pin "36") (pinfunction "P22_36") (pintype "unspecified"))
      (node (ref "U4") (pin "3") (pinfunction "SCL_3") (pintype "unspecified"))
      (node (ref "U8") (pin "1") (pinfunction "L1_1") (pintype "unspecified"))
    )
    (net (code "54") (name "SDA") (class "Default")
      (node (ref "I2C") (pin "2") (pinfunction "2_2") (pintype "unspecified"))
      (node (ref "U5") (pin "7") (pinfunction "SDA_7") (pintype "unspecified"))
      (node (ref "U6") (pin "7") (pinfunction "SDA_7") (pintype "unspecified"))
      (node (ref "U8") (pin "11") (pinfunction "H2_11") (pintype "unspecified"))
    )
    (net (code "55") (name "SDA_3V3") (class "Default")
      (node (ref "U1") (pin "33") (pinfunction "P21_33") (pintype "unspecified"))
      (node (ref "U4") (pin "4") (pinfunction "SDA_4") (pintype "unspecified"))
      (node (ref "U8") (pin "2") (pinfunction "L2_2") (pintype "unspecified"))
    )
    (net (code "56") (name "TX") (class "Default")
      (node (ref "SERIAL") (pin "1") (pinfunction "1_1") (pintype "unspecified"))
      (node (ref "U1") (pin "35") (pinfunction "TX_35") (pintype "unspecified"))
    )
    (net (code "57") (name "VCC") (class "Default")
      (node (ref "C_POWER1") (pin "2") (pinfunction "2_2") (pintype "unspecified"))
      (node (ref "DRIVER1") (pin "16") (pinfunction "VSS_16") (pintype "unspecified"))
      (node (ref "POWER") (pin "1") (pinfunction "1_1") (pintype "unspecified"))
      (node (ref "U1") (pin "1") (pinfunction "Vin_(5V)_1") (pintype "unspecified"))
      (node (ref "U2") (pin "1") (pinfunction "IN_1") (pintype "passive"))
      (node (ref "U3") (pin "1") (pinfunction "IP+_1") (pintype "input"))
    )
    (net (code "58") (name "VOLTAGE_IN") (class "Default")
      (node (ref "R3") (pin "2") (pinfunction "2_2") (pintype "unspecified"))
      (node (ref "R4") (pin "2") (pinfunction "2_2") (pintype "unspecified"))
      (node (ref "U1") (pin "17") (pinfunction "SVP_17") (pintype "unspecified"))
    )
    (net (code "59") (name "V_BATTERY") (class "Default")
      (node (ref "BATTERY") (pin "1") (pinfunction "1_1") (pintype "unspecified"))
      (node (ref "KEY3") (pin "1") (pinfunction "1_1") (pintype "input"))
      (node (ref "Q1") (pin "3") (pinfunction "S_3") (pintype "unspecified"))
      (node (ref "R2") (pin "2") (pinfunction "2_2") (pintype "unspecified"))
    )
    (net (code "60") (name "unconnected-(KEY1-Pad2)") (class "Default")
      (node (ref "KEY1") (pin "2") (pinfunction "2_2") (pintype "input+no_connect"))
    )
    (net (code "61") (name "unconnected-(KEY1-Pad4)") (class "Default")
      (node (ref "KEY1") (pin "4") (pinfunction "4_4") (pintype "input+no_connect"))
    )
    (net (code "62") (name "unconnected-(KEY2-Pad2)") (class "Default")
      (node (ref "KEY2") (pin "2") (pinfunction "2_2") (pintype "input+no_connect"))
    )
    (net (code "63") (name "unconnected-(KEY2-Pad4)") (class "Default")
      (node (ref "KEY2") (pin "4") (pinfunction "4_4") (pintype "input+no_connect"))
    )
    (net (code "64") (name "unconnected-(KEY3-Pad2)") (class "Default")
      (node (ref "KEY3") (pin "2") (pinfunction "2_2") (pintype "input+no_connect"))
    )
    (net (code "65") (name "unconnected-(KEY3-Pad4)") (class "Default")
      (node (ref "KEY3") (pin "4") (pinfunction "4_4") (pintype "input+no_connect"))
    )
    (net (code "66") (name "unconnected-(U1-CLK-Pad20)") (class "Default")
      (node (ref "U1") (pin "20") (pinfunction "CLK_20") (pintype "unspecified+no_connect"))
    )
    (net (code "67") (name "unconnected-(U1-CMD-Pad2)") (class "Default")
      (node (ref "U1") (pin "2") (pinfunction "CMD_2") (pintype "unspecified+no_connect"))
    )
    (net (code "68") (name "unconnected-(U1-SD0-Pad21)") (class "Default")
      (node (ref "U1") (pin "21") (pinfunction "SD0_21") (pintype "unspecified+no_connect"))
    )
    (net (code "69") (name "unconnected-(U1-SD1-Pad22)") (class "Default")
      (node (ref "U1") (pin "22") (pinfunction "SD1_22") (pintype "unspecified+no_connect"))
    )
    (net (code "70") (name "unconnected-(U1-SD2-Pad4)") (class "Default")
      (node (ref "U1") (pin "4") (pinfunction "SD2_4") (pintype "unspecified+no_connect"))
    )
    (net (code "71") (name "unconnected-(U1-SD3-Pad3)") (class "Default")
      (node (ref "U1") (pin "3") (pinfunction "SD3_3") (pintype "unspecified+no_connect"))
    )
    (net (code "72") (name "unconnected-(U4-AD0-Pad7)") (class "Default")
      (node (ref "U4") (pin "7") (pinfunction "AD0_7") (pintype "unspecified+no_connect"))
    )
    (net (code "73") (name "unconnected-(U4-INT-Pad8)") (class "Default")
      (node (ref "U4") (pin "8") (pinfunction "INT_8") (pintype "unspecified+no_connect"))
    )
    (net (code "74") (name "unconnected-(U4-XCL-Pad6)") (class "Default")
      (node (ref "U4") (pin "6") (pinfunction "XCL_6") (pintype "unspecified+no_connect"))
    )
    (net (code "75") (name "unconnected-(U4-XDA-Pad5)") (class "Default")
      (node (ref "U4") (pin "5") (pinfunction "XDA_5") (pintype "unspecified+no_connect"))
    )
  )
)
